# USB.net
KiCad netlist of a schematic drawn in Altium Designer
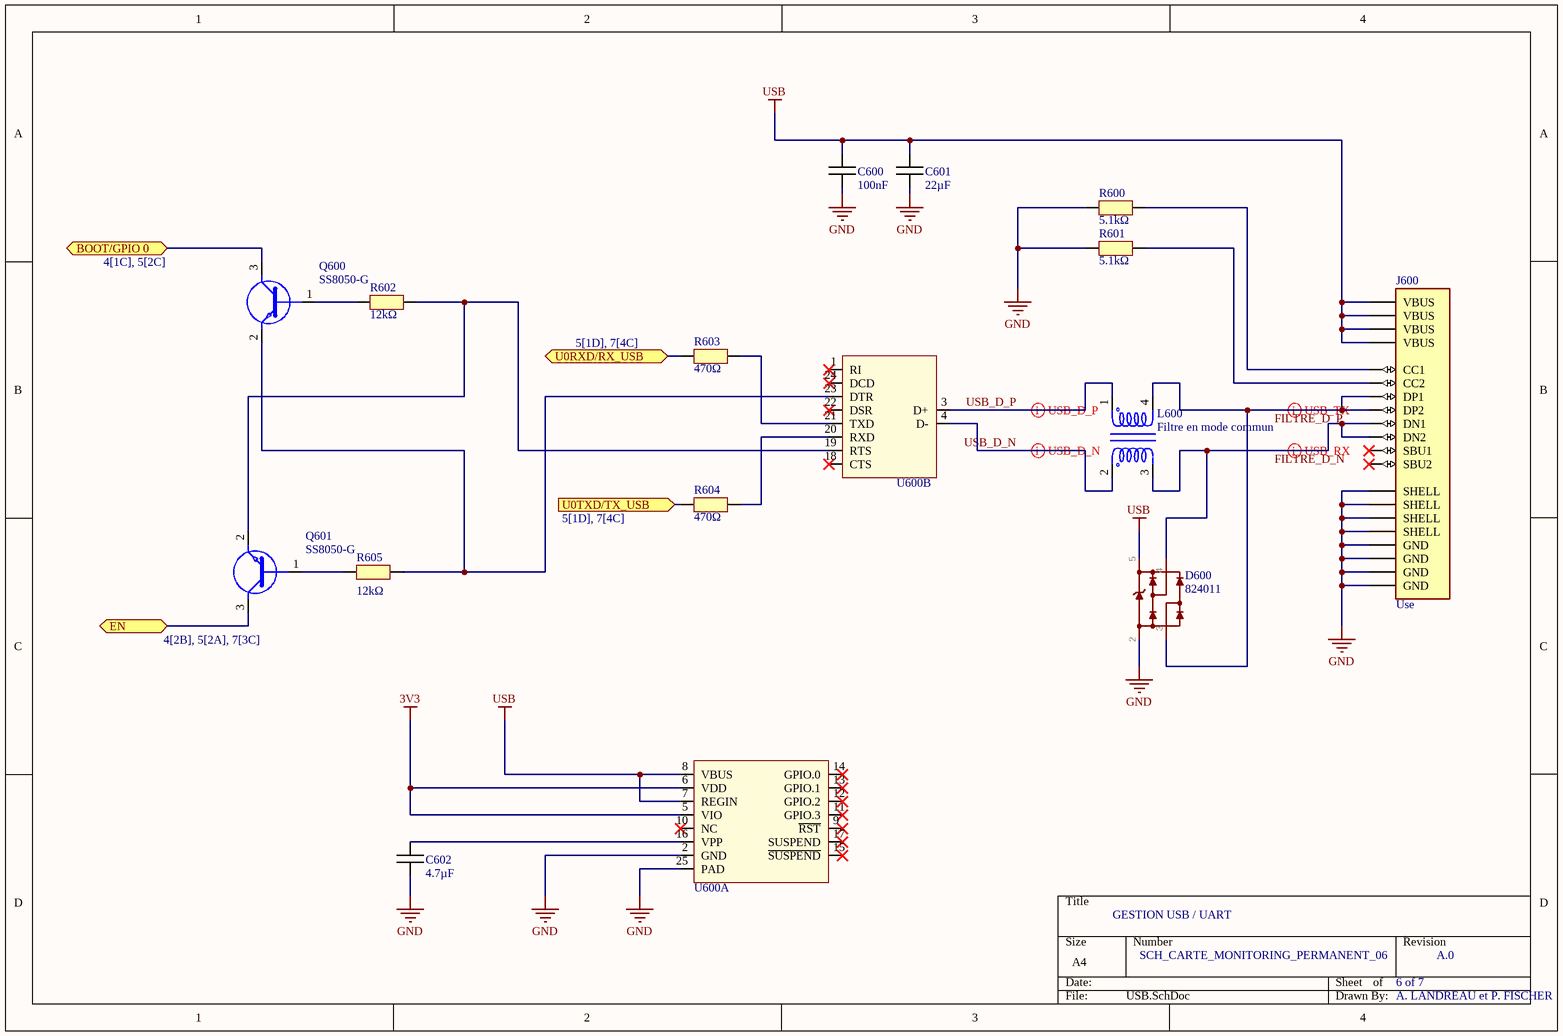
[diagram p0: USB.SchDoc]

(export (version "E")
  (design (tool "Eeschema 10.0.6"))
  (components
    (comp (ref "C600")
      (value "100nF")
      (footprint "CAPC1005X06N")
      (libsource (lib "SCHLibrary") (part "Capacitor"))
    )
    (comp (ref "C601")
      (value "22µF")
      (footprint "CAPC1005X06N")
      (libsource (lib "SCHLibrary") (part "Capacitor"))
    )
    (comp (ref "C602")
      (value "4.7µF")
      (footprint "CAPC1005X06N")
      (libsource (lib "SCHLibrary") (part "Capacitor"))
    )
    (comp (ref "D600") (value "824011") (footprint "824011") (libsource (lib "SCHLibrary") (part "824011")))
    (comp (ref "J600")
      (value "Use")
      (footprint "USB4085-GF-A")
      (description "Connecteurs USB USB Type C, 2.0, Rec, TH , G/F, RA , Top Mnt, T & R")
      (libsource (lib "SCHLibrary") (part "USB4085-GF-A"))
    )
    (comp (ref "L600")
      (value "Filtre en mode commun")
      (footprint "744232090")
      (description "Bobines / filtres en mode commun WE-CNSW 1206 370mA 90Ohm 100MHz AECQ200")
      (libsource (lib "SCHLibrary") (part "744232090"))
    )
    (comp (ref "Q600")
      (value "SS8050-G")
      (footprint "SS8050-G")
      (description "Bipolar Transistors - BJT NPN TRANSISTOR 1.5A 40V")
      (libsource (lib "SCHLibrary") (part "SS8050-G"))
    )
    (comp (ref "Q601")
      (value "SS8050-G")
      (footprint "SS8050-G")
      (description "Bipolar Transistors - BJT NPN TRANSISTOR 1.5A 40V")
      (libsource (lib "SCHLibrary") (part "SS8050-G"))
    )
    (comp (ref "R600")
      (value "5.1kΩ")
      (footprint "RESC1005X06N")
      (libsource (lib "SCHLibrary") (part "Resistor"))
    )
    (comp (ref "R601")
      (value "5.1kΩ")
      (footprint "RESC1005X06N")
      (libsource (lib "SCHLibrary") (part "Resistor"))
    )
    (comp (ref "R602")
      (value "12kΩ")
      (footprint "RESC1005X06N")
      (libsource (lib "SCHLibrary") (part "Resistor"))
    )
    (comp (ref "R603")
      (value "470Ω")
      (footprint "RESC1005X06N")
      (libsource (lib "SCHLibrary") (part "Resistor"))
    )
    (comp (ref "R604")
      (value "470Ω")
      (footprint "RESC1005X06N")
      (libsource (lib "SCHLibrary") (part "Resistor"))
    )
    (comp (ref "R605")
      (value "12kΩ")
      (footprint "RESC1005X06N")
      (libsource (lib "SCHLibrary") (part "Resistor"))
    )
    (comp (ref "U600")
      (value "CP2104-F03-GM")
      (footprint "PQFN50P400X400X80_HS-25N")
      (description "USB Bridge, USB to UART USB 2.0 UART Interface 24-QFN (4x4)")
      (libsource (lib "SCHLibrary") (part "USBBridge"))
    )
  )
  (nets
    (net (code "1") (name "/BOOT{slash}GPIO 0") (class "Default")
      (node (ref "Q600") (pin "3") (pinfunction "C_3") (pintype "passive"))
    )
    (net (code "2") (name "/EN") (class "Default")
      (node (ref "Q601") (pin "3") (pinfunction "C_3") (pintype "passive"))
    )
    (net (code "3") (name "/FILTRE_D_N") (class "Default")
      (node (ref "D600") (pin "4") (pinfunction "2_4") (pintype "passive"))
      (node (ref "J600") (pin "A7") (pinfunction "DN1_A7") (pintype "bidirectional"))
      (node (ref "J600") (pin "B7") (pinfunction "DN2_B7") (pintype "bidirectional"))
      (node (ref "L600") (pin "3") (pinfunction "3_3") (pintype "passive"))
    )
    (net (code "4") (name "/FILTRE_D_P") (class "Default")
      (node (ref "D600") (pin "3") (pinfunction "1_3") (pintype "passive"))
      (node (ref "J600") (pin "A6") (pinfunction "DP1_A6") (pintype "bidirectional"))
      (node (ref "J600") (pin "B6") (pinfunction "DP2_B6") (pintype "bidirectional"))
      (node (ref "L600") (pin "4") (pinfunction "4_4") (pintype "passive"))
    )
    (net (code "5") (name "/U0RXD{slash}RX_USB") (class "Default")
      (node (ref "R603") (pin "1") (pinfunction "1_1") (pintype "passive"))
    )
    (net (code "6") (name "/U0TXD{slash}TX_USB") (class "Default")
      (node (ref "R604") (pin "1") (pinfunction "1_1") (pintype "passive"))
    )
    (net (code "7") (name "/USB_D_N") (class "Default")
      (node (ref "L600") (pin "2") (pinfunction "2_2") (pintype "passive"))
      (node (ref "U600") (pin "4") (pinfunction "D-_4") (pintype "passive"))
    )
    (net (code "8") (name "/USB_D_P") (class "Default")
      (node (ref "L600") (pin "1") (pinfunction "1_1") (pintype "passive"))
      (node (ref "U600") (pin "3") (pinfunction "D+_3") (pintype "passive"))
    )
    (net (code "9") (name "3V3") (class "Default")
      (node (ref "U600") (pin "5") (pinfunction "VIO_5") (pintype "passive"))
      (node (ref "U600") (pin "6") (pinfunction "VDD_6") (pintype "passive"))
    )
    (net (code "10") (name "GND") (class "Default")
      (node (ref "C600") (pin "2") (pinfunction "2_2") (pintype "passive"))
      (node (ref "C601") (pin "2") (pinfunction "2_2") (pintype "passive"))
      (node (ref "C602") (pin "2") (pinfunction "2_2") (pintype "passive"))
      (node (ref "D600") (pin "2") (pinfunction "GND_2") (pintype "power_in"))
      (node (ref "J600") (pin "A1") (pinfunction "GND_A1") (pintype "power_in"))
      (node (ref "J600") (pin "A12") (pinfunction "GND_A12") (pintype "power_in"))
      (node (ref "J600") (pin "B1") (pinfunction "GND_B1") (pintype "power_in"))
      (node (ref "J600") (pin "B12") (pinfunction "GND_B12") (pintype "power_in"))
      (node (ref "J600") (pin "S1") (pinfunction "SHELL_S1") (pintype "passive"))
      (node (ref "J600") (pin "S2") (pinfunction "SHELL_S2") (pintype "passive"))
      (node (ref "J600") (pin "S3") (pinfunction "SHELL_S3") (pintype "passive"))
      (node (ref "J600") (pin "S4") (pinfunction "SHELL_S4") (pintype "passive"))
      (node (ref "R600") (pin "1") (pinfunction "1_1") (pintype "passive"))
      (node (ref "R601") (pin "1") (pinfunction "1_1") (pintype "passive"))
      (node (ref "U600") (pin "2") (pinfunction "GND_2") (pintype "passive"))
      (node (ref "U600") (pin "25") (pinfunction "PAD_25") (pintype "passive"))
    )
    (net (code "11") (name "Net-(J600-CC1)") (class "Default")
      (node (ref "J600") (pin "A5") (pinfunction "CC1_A5") (pintype "bidirectional"))
      (node (ref "R600") (pin "2") (pinfunction "2_2") (pintype "passive"))
    )
    (net (code "12") (name "Net-(J600-CC2)") (class "Default")
      (node (ref "J600") (pin "B5") (pinfunction "CC2_B5") (pintype "bidirectional"))
      (node (ref "R601") (pin "2") (pinfunction "2_2") (pintype "passive"))
    )
    (net (code "13") (name "Net-(Q600-B)") (class "Default")
      (node (ref "Q600") (pin "1") (pinfunction "B_1") (pintype "passive"))
      (node (ref "R602") (pin "1") (pinfunction "1_1") (pintype "passive"))
    )
    (net (code "14") (name "Net-(Q600-E)") (class "Default")
      (node (ref "Q600") (pin "2") (pinfunction "E_2") (pintype "passive"))
      (node (ref "R605") (pin "2") (pinfunction "2_2") (pintype "passive"))
      (node (ref "U600") (pin "23") (pinfunction "DTR_23") (pintype "passive"))
    )
    (net (code "15") (name "Net-(Q601-B)") (class "Default")
      (node (ref "Q601") (pin "1") (pinfunction "B_1") (pintype "passive"))
      (node (ref "R605") (pin "1") (pinfunction "1_1") (pintype "passive"))
    )
    (net (code "16") (name "Net-(Q601-E)") (class "Default")
      (node (ref "Q601") (pin "2") (pinfunction "E_2") (pintype "passive"))
      (node (ref "R602") (pin "2") (pinfunction "2_2") (pintype "passive"))
      (node (ref "U600") (pin "19") (pinfunction "RTS_19") (pintype "passive"))
    )
    (net (code "17") (name "Net-(U600A-VPP)") (class "Default")
      (node (ref "C602") (pin "1") (pinfunction "1_1") (pintype "passive"))
      (node (ref "U600") (pin "16") (pinfunction "VPP_16") (pintype "passive"))
    )
    (net (code "18") (name "Net-(U600B-RXD)") (class "Default")
      (node (ref "R604") (pin "2") (pinfunction "2_2") (pintype "passive"))
      (node (ref "U600") (pin "20") (pinfunction "RXD_20") (pintype "passive"))
    )
    (net (code "19") (name "Net-(U600B-TXD)") (class "Default")
      (node (ref "R603") (pin "2") (pinfunction "2_2") (pintype "passive"))
      (node (ref "U600") (pin "21") (pinfunction "TXD_21") (pintype "passive"))
    )
    (net (code "20") (name "USB") (class "Default")
      (node (ref "C600") (pin "1") (pinfunction "1_1") (pintype "passive"))
      (node (ref "C601") (pin "1") (pinfunction "1_1") (pintype "passive"))
      (node (ref "D600") (pin "5") (pinfunction "VDD_5") (pintype "power_in"))
      (node (ref "J600") (pin "A4") (pinfunction "VBUS_A4") (pintype "power_in"))
      (node (ref "J600") (pin "A9") (pinfunction "VBUS_A9") (pintype "power_in"))
      (node (ref "J600") (pin "B4") (pinfunction "VBUS_B4") (pintype "power_in"))
      (node (ref "J600") (pin "B9") (pinfunction "VBUS_B9") (pintype "power_in"))
      (node (ref "U600") (pin "7") (pinfunction "REGIN_7") (pintype "passive"))
      (node (ref "U600") (pin "8") (pinfunction "VBUS_8") (pintype "passive"))
    )
    (net (code "21") (name "unconnected-(J600-SBU1-PadA8)") (class "Default")
      (node (ref "J600") (pin "A8") (pinfunction "SBU1_A8") (pintype "bidirectional+no_connect"))
    )
    (net (code "22") (name "unconnected-(J600-SBU2-PadB8)") (class "Default")
      (node (ref "J600") (pin "B8") (pinfunction "SBU2_B8") (pintype "bidirectional+no_connect"))
    )
    (net (code "23") (name "unconnected-(U600A-GPIO.0-Pad14)") (class "Default")
      (node (ref "U600") (pin "14") (pinfunction "GPIO.0_14") (pintype "passive+no_connect"))
    )
    (net (code "24") (name "unconnected-(U600A-GPIO.1-Pad13)") (class "Default")
      (node (ref "U600") (pin "13") (pinfunction "GPIO.1_13") (pintype "passive+no_connect"))
    )
    (net (code "25") (name "unconnected-(U600A-GPIO.2-Pad12)") (class "Default")
      (node (ref "U600") (pin "12") (pinfunction "GPIO.2_12") (pintype "passive+no_connect"))
    )
    (net (code "26") (name "unconnected-(U600A-GPIO.3-Pad11)") (class "Default")
      (node (ref "U600") (pin "11") (pinfunction "GPIO.3_11") (pintype "passive+no_connect"))
    )
    (net (code "27") (name "unconnected-(U600A-NC-Pad10)") (class "Default")
      (node (ref "U600") (pin "10") (pinfunction "NC_10") (pintype "passive+no_connect"))
    )
    (net (code "28") (name "unconnected-(U600A-SUSPEND-Pad17)") (class "Default")
      (node (ref "U600") (pin "17") (pinfunction "SUSPEND_17") (pintype "passive+no_connect"))
    )
    (net (code "29") (name "unconnected-(U600A-~{RST}-Pad9)") (class "Default")
      (node (ref "U600") (pin "9") (pinfunction "~{RST}_9") (pintype "passive+no_connect"))
    )
    (net (code "30") (name "unconnected-(U600A-~{SUSPEND}-Pad15)") (class "Default")
      (node (ref "U600") (pin "15") (pinfunction "~{SUSPEND}_15") (pintype "passive+no_connect"))
    )
    (net (code "31") (name "unconnected-(U600B-CTS-Pad18)") (class "Default")
      (node (ref "U600") (pin "18") (pinfunction "CTS_18") (pintype "passive+no_connect"))
    )
    (net (code "32") (name "unconnected-(U600B-DCD-Pad24)") (class "Default")
      (node (ref "U600") (pin "24") (pinfunction "DCD_24") (pintype "passive+no_connect"))
    )
    (net (code "33") (name "unconnected-(U600B-DSR-Pad22)") (class "Default")
      (node (ref "U600") (pin "22") (pinfunction "DSR_22") (pintype "passive+no_connect"))
    )
    (net (code "34") (name "unconnected-(U600B-RI-Pad1)") (class "Default")
      (node (ref "U600") (pin "1") (pinfunction "RI_1") (pintype "passive+no_connect"))
    )
  )
)
